# USBSerial.net
KiCad netlist of a schematic drawn in EAGLE
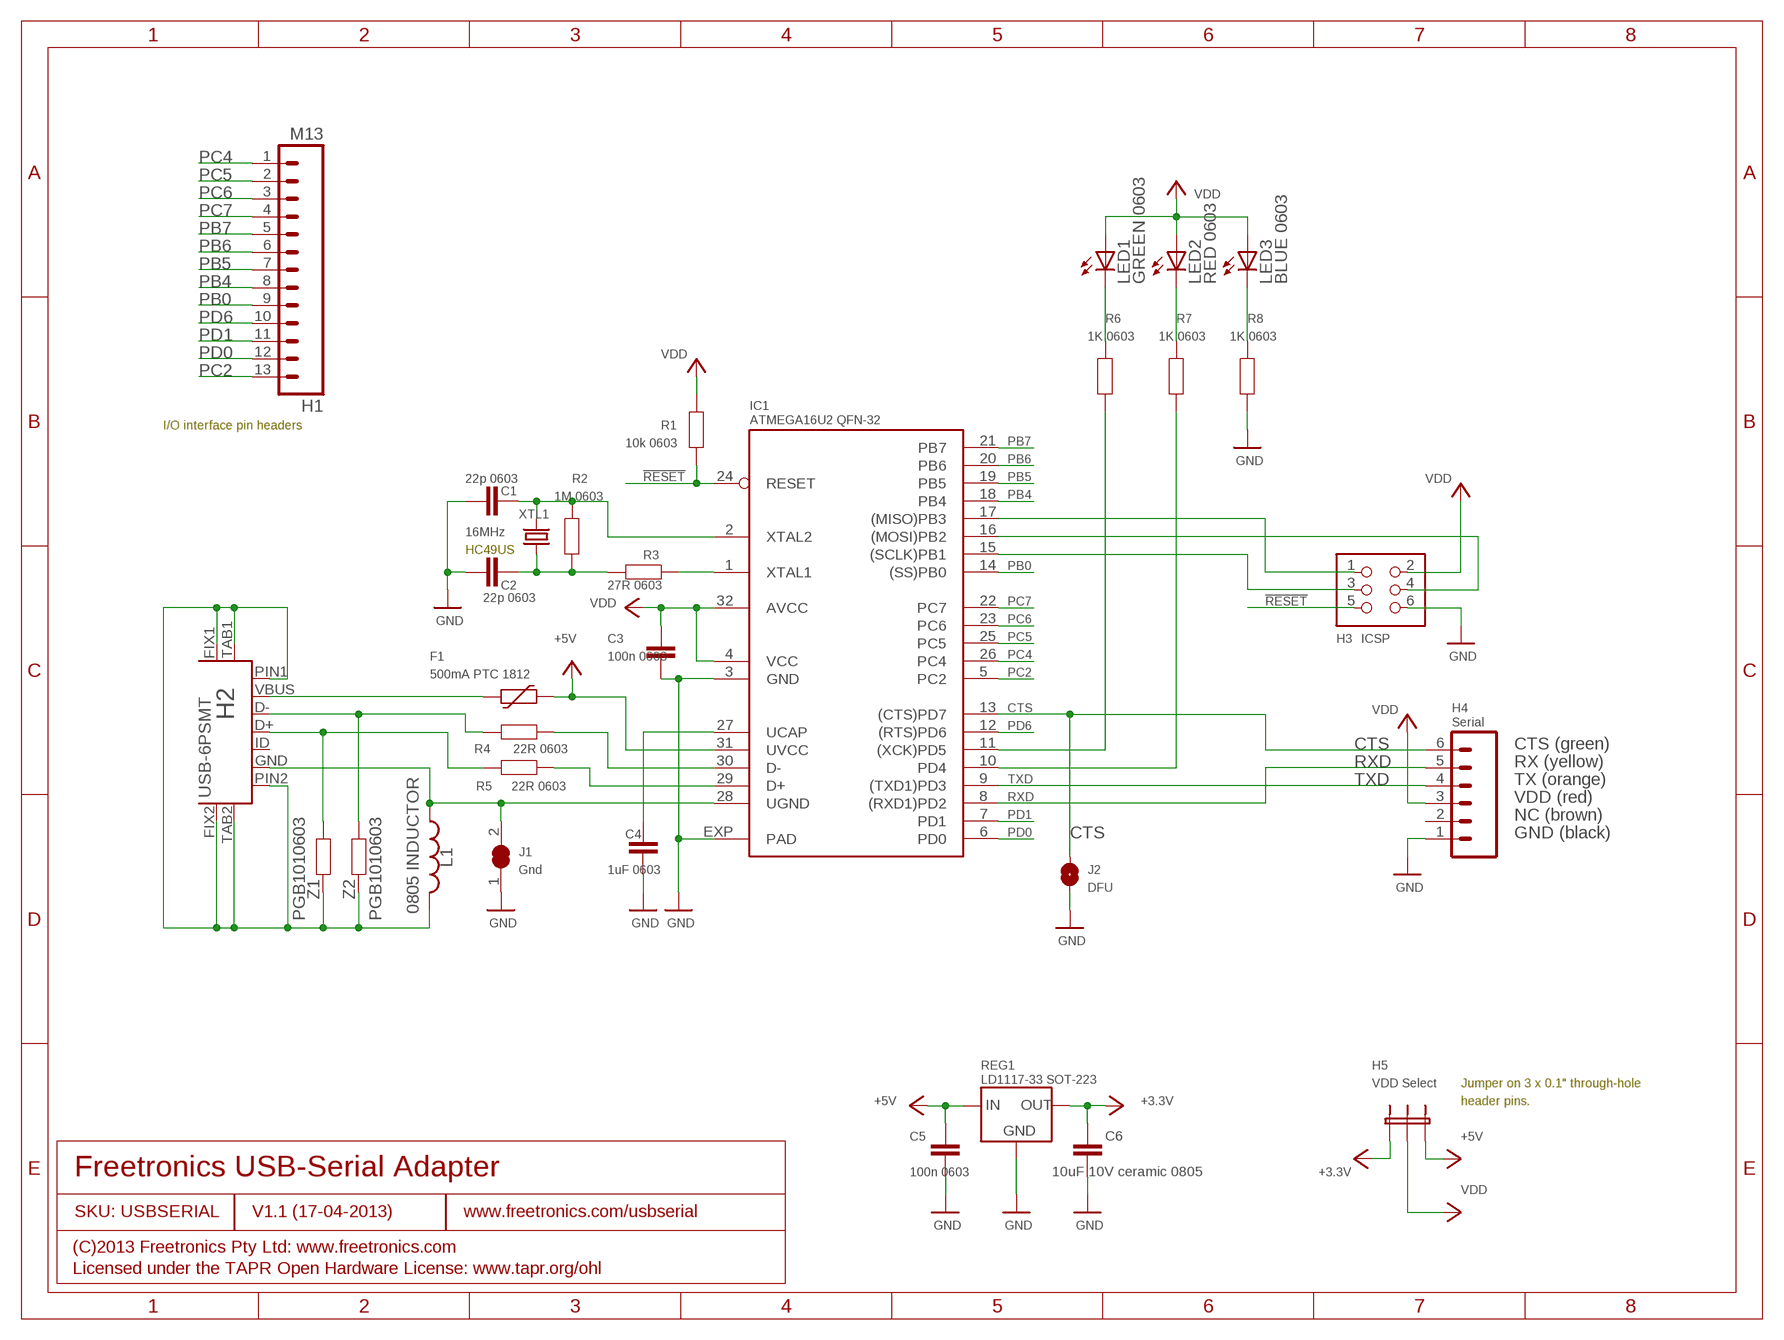
[diagram p0: schematic, sheet 1]

(export (version "E")
  (design (tool "Eeschema 10.0.6"))
  (components
    (comp (ref "C1")
      (value "22p 0603")
      (footprint "eagle-import:0603")
      (libsource (lib "eagle-import") (part "CAP0603"))
    )
    (comp (ref "C2")
      (value "22p 0603")
      (footprint "eagle-import:0603")
      (libsource (lib "eagle-import") (part "CAP0603"))
    )
    (comp (ref "C3")
      (value "100n 0603")
      (footprint "eagle-import:0603")
      (libsource (lib "eagle-import") (part "CAP0603"))
    )
    (comp (ref "C4")
      (value "1uF 0603")
      (footprint "eagle-import:0603")
      (libsource (lib "eagle-import") (part "CAP0603"))
    )
    (comp (ref "C5")
      (value "100n 0603")
      (footprint "eagle-import:0603")
      (libsource (lib "eagle-import") (part "CAP0603"))
    )
    (comp (ref "C6")
      (value "10uF 10V ceramic 0805")
      (footprint "eagle-import:C0805")
      (libsource (lib "eagle-import") (part "C-EUC0805"))
    )
    (comp (ref "F1")
      (value "500mA PTC 1812")
      (footprint "eagle-import:1812")
      (libsource (lib "eagle-import") (part "PTC"))
    )
    (comp (ref "H1")
      (value "M13")
      (footprint "eagle-import:1X13")
      (libsource (lib "eagle-import") (part "M13"))
    )
    (comp (ref "H2")
      (value "USB-6PSMT")
      (footprint "eagle-import:USB-MICROB-MB05PMXX")
      (libsource (lib "eagle-import") (part "USB-6PSMT"))
    )
    (comp (ref "H3")
      (value "ICSP")
      (footprint "eagle-import:HEADER_2X3")
      (libsource (lib "eagle-import") (part "HEADER_2X3"))
    )
    (comp (ref "H4")
      (value "Serial")
      (footprint "eagle-import:1X06")
      (libsource (lib "eagle-import") (part "M06SIP"))
    )
    (comp (ref "H5")
      (value "VDD Select")
      (footprint "eagle-import:JUMPER_SPDT")
      (libsource (lib "eagle-import") (part "JUMPER_SPDT"))
    )
    (comp (ref "IC1")
      (value "ATMEGA16U2 QFN-32")
      (footprint "eagle-import:ATMEL_QFN32")
      (libsource (lib "eagle-import") (part "ATMEL_ATMEGA8U2-MUQFN"))
    )
    (comp (ref "J1")
      (value "Gnd")
      (footprint "eagle-import:SJC")
      (libsource (lib "eagle-import") (part "SJCN"))
    )
    (comp (ref "J2") (value "DFU") (footprint "eagle-import:SJ") (libsource (lib "eagle-import") (part "SJ")))
    (comp (ref "L1")
      (value "0805 INDUCTOR")
      (footprint "eagle-import:0805-LARGE")
      (libsource (lib "eagle-import") (part "INDUCTOR0805-LARGE"))
    )
    (comp (ref "LED1")
      (value "GREEN 0603")
      (footprint "eagle-import:LED-0603")
      (libsource (lib "eagle-import") (part "LED0603"))
    )
    (comp (ref "LED2")
      (value "RED 0603")
      (footprint "eagle-import:LED-0603")
      (libsource (lib "eagle-import") (part "LED0603"))
    )
    (comp (ref "LED3")
      (value "BLUE 0603")
      (footprint "eagle-import:LED-0603")
      (libsource (lib "eagle-import") (part "LED0603"))
    )
    (comp (ref "R1")
      (value "10k 0603")
      (footprint "eagle-import:0603")
      (libsource (lib "eagle-import") (part "RESISTOR0603"))
    )
    (comp (ref "R2")
      (value "1M 0603")
      (footprint "eagle-import:0603")
      (libsource (lib "eagle-import") (part "RESISTOR0603"))
    )
    (comp (ref "R3")
      (value "27R 0603")
      (footprint "eagle-import:0603")
      (libsource (lib "eagle-import") (part "RESISTOR0603"))
    )
    (comp (ref "R4")
      (value "22R 0603")
      (footprint "eagle-import:0603")
      (libsource (lib "eagle-import") (part "RESISTOR0603"))
    )
    (comp (ref "R5")
      (value "22R 0603")
      (footprint "eagle-import:0603")
      (libsource (lib "eagle-import") (part "RESISTOR0603"))
    )
    (comp (ref "R6")
      (value "1K 0603")
      (footprint "eagle-import:0603")
      (libsource (lib "eagle-import") (part "RESISTOR0603"))
    )
    (comp (ref "R7")
      (value "1K 0603")
      (footprint "eagle-import:0603")
      (libsource (lib "eagle-import") (part "RESISTOR0603"))
    )
    (comp (ref "R8")
      (value "1K 0603")
      (footprint "eagle-import:0603")
      (libsource (lib "eagle-import") (part "RESISTOR0603"))
    )
    (comp (ref "REG1")
      (value "LD1117-33 SOT-223")
      (footprint "eagle-import:SOT-223")
      (libsource (lib "eagle-import") (part "LD1117-FIXED"))
    )
    (comp (ref "XTL1")
      (value "16MHz")
      (footprint "eagle-import:HC49US")
      (libsource (lib "eagle-import") (part "CRYSTALHC49US"))
    )
    (comp (ref "Z1")
      (value "PGB1010603")
      (footprint "eagle-import:0603")
      (libsource (lib "eagle-import") (part "RESISTOR0603"))
    )
    (comp (ref "Z2")
      (value "PGB1010603")
      (footprint "eagle-import:0603")
      (libsource (lib "eagle-import") (part "RESISTOR0603"))
    )
  )
  (nets
    (net (code "1") (name "+3.3V") (class "Default")
      (node (ref "C6") (pin "1") (pinfunction "1_1") (pintype "passive"))
      (node (ref "H5") (pin "1") (pinfunction "1_1") (pintype "passive"))
      (node (ref "REG1") (pin "2") (pinfunction "OUT_2") (pintype "power_in"))
      (node (ref "REG1") (pin "4") (pinfunction "OUT_4") (pintype "power_in"))
    )
    (net (code "2") (name "+5V") (class "Default")
      (node (ref "C5") (pin "1") (pinfunction "1_1") (pintype "passive"))
      (node (ref "F1") (pin "2") (pinfunction "P$2_2") (pintype "bidirectional"))
      (node (ref "H5") (pin "3") (pinfunction "3_3") (pintype "passive"))
      (node (ref "IC1") (pin "31") (pinfunction "UVCC_31") (pintype "power_in"))
      (node (ref "REG1") (pin "3") (pinfunction "IN_3") (pintype "input"))
    )
    (net (code "3") (name "/CTS") (class "Default")
      (node (ref "H4") (pin "6") (pinfunction "6_6") (pintype "passive"))
      (node (ref "IC1") (pin "13") (pinfunction "(CTS)PD7_13") (pintype "bidirectional"))
      (node (ref "J2") (pin "2") (pinfunction "2_2") (pintype "passive"))
    )
    (net (code "4") (name "/PB0") (class "Default")
      (node (ref "H1") (pin "9") (pinfunction "9_9") (pintype "passive"))
      (node (ref "IC1") (pin "14") (pinfunction "(SS)PB0_14") (pintype "bidirectional"))
    )
    (net (code "5") (name "/PB4") (class "Default")
      (node (ref "H1") (pin "8") (pinfunction "8_8") (pintype "passive"))
      (node (ref "IC1") (pin "18") (pinfunction "PB4_18") (pintype "bidirectional"))
    )
    (net (code "6") (name "/PB5") (class "Default")
      (node (ref "H1") (pin "7") (pinfunction "7_7") (pintype "passive"))
      (node (ref "IC1") (pin "19") (pinfunction "PB5_19") (pintype "bidirectional"))
    )
    (net (code "7") (name "/PB6") (class "Default")
      (node (ref "H1") (pin "6") (pinfunction "6_6") (pintype "passive"))
      (node (ref "IC1") (pin "20") (pinfunction "PB6_20") (pintype "bidirectional"))
    )
    (net (code "8") (name "/PB7") (class "Default")
      (node (ref "H1") (pin "5") (pinfunction "5_5") (pintype "passive"))
      (node (ref "IC1") (pin "21") (pinfunction "PB7_21") (pintype "bidirectional"))
    )
    (net (code "9") (name "/PC2") (class "Default")
      (node (ref "H1") (pin "13") (pinfunction "13_13") (pintype "passive"))
      (node (ref "IC1") (pin "5") (pinfunction "PC2_5") (pintype "bidirectional"))
    )
    (net (code "10") (name "/PC4") (class "Default")
      (node (ref "H1") (pin "1") (pinfunction "1_1") (pintype "passive"))
      (node (ref "IC1") (pin "26") (pinfunction "PC4_26") (pintype "bidirectional"))
    )
    (net (code "11") (name "/PC5") (class "Default")
      (node (ref "H1") (pin "2") (pinfunction "2_2") (pintype "passive"))
      (node (ref "IC1") (pin "25") (pinfunction "PC5_25") (pintype "bidirectional"))
    )
    (net (code "12") (name "/PC6") (class "Default")
      (node (ref "H1") (pin "3") (pinfunction "3_3") (pintype "passive"))
      (node (ref "IC1") (pin "23") (pinfunction "PC6_23") (pintype "bidirectional"))
    )
    (net (code "13") (name "/PC7") (class "Default")
      (node (ref "H1") (pin "4") (pinfunction "4_4") (pintype "passive"))
      (node (ref "IC1") (pin "22") (pinfunction "PC7_22") (pintype "bidirectional"))
    )
    (net (code "14") (name "/PD0") (class "Default")
      (node (ref "H1") (pin "12") (pinfunction "12_12") (pintype "passive"))
      (node (ref "IC1") (pin "6") (pinfunction "PD0_6") (pintype "bidirectional"))
    )
    (net (code "15") (name "/PD1") (class "Default")
      (node (ref "H1") (pin "11") (pinfunction "11_11") (pintype "passive"))
      (node (ref "IC1") (pin "7") (pinfunction "PD1_7") (pintype "bidirectional"))
    )
    (net (code "16") (name "/PD6") (class "Default")
      (node (ref "H1") (pin "10") (pinfunction "10_10") (pintype "passive"))
      (node (ref "IC1") (pin "12") (pinfunction "(RTS)PD6_12") (pintype "bidirectional"))
    )
    (net (code "17") (name "/RXD") (class "Default")
      (node (ref "H4") (pin "5") (pinfunction "5_5") (pintype "passive"))
      (node (ref "IC1") (pin "8") (pinfunction "(RXD1)PD2_8") (pintype "bidirectional"))
    )
    (net (code "18") (name "/TXD") (class "Default")
      (node (ref "H4") (pin "4") (pinfunction "4_4") (pintype "passive"))
      (node (ref "IC1") (pin "9") (pinfunction "(TXD1)PD3_9") (pintype "bidirectional"))
    )
    (net (code "19") (name "/~{RESET}") (class "Default")
      (node (ref "H3") (pin "5") (pinfunction "5_5") (pintype "passive"))
      (node (ref "IC1") (pin "24") (pinfunction "RESET_24") (pintype "input"))
      (node (ref "R1") (pin "1") (pinfunction "1_1") (pintype "passive"))
    )
    (net (code "20") (name "GND") (class "Default")
      (node (ref "C1") (pin "1") (pinfunction "1_1") (pintype "passive"))
      (node (ref "C2") (pin "1") (pinfunction "1_1") (pintype "passive"))
      (node (ref "C3") (pin "2") (pinfunction "2_2") (pintype "passive"))
      (node (ref "C4") (pin "2") (pinfunction "2_2") (pintype "passive"))
      (node (ref "C5") (pin "2") (pinfunction "2_2") (pintype "passive"))
      (node (ref "C6") (pin "2") (pinfunction "2_2") (pintype "passive"))
      (node (ref "H3") (pin "6") (pinfunction "6_6") (pintype "passive"))
      (node (ref "H4") (pin "1") (pinfunction "1_1") (pintype "passive"))
      (node (ref "IC1") (pin "3") (pinfunction "GND_3") (pintype "power_in"))
      (node (ref "IC1") (pin "EXP") (pinfunction "PAD_EXP") (pintype "power_in"))
      (node (ref "J1") (pin "1") (pinfunction "1_1") (pintype "passive"))
      (node (ref "J2") (pin "1") (pinfunction "1_1") (pintype "passive"))
      (node (ref "R8") (pin "1") (pinfunction "1_1") (pintype "passive"))
      (node (ref "REG1") (pin "1") (pinfunction "GND_1") (pintype "input"))
    )
    (net (code "21") (name "Net-(C2-Pad2)") (class "Default")
      (node (ref "C2") (pin "2") (pinfunction "2_2") (pintype "passive"))
      (node (ref "R2") (pin "1") (pinfunction "1_1") (pintype "passive"))
      (node (ref "R3") (pin "2") (pinfunction "2_2") (pintype "passive"))
      (node (ref "XTL1") (pin "1") (pinfunction "1_1") (pintype "passive"))
    )
    (net (code "22") (name "Net-(F1-P$1)") (class "Default")
      (node (ref "F1") (pin "1") (pinfunction "P$1_1") (pintype "bidirectional"))
      (node (ref "H2") (pin "VBUS") (pinfunction "VBUS_VBUS") (pintype "bidirectional"))
    )
    (net (code "23") (name "Net-(H2-PadD+)") (class "Default")
      (node (ref "H2") (pin "D+") (pinfunction "D+_D+") (pintype "bidirectional"))
      (node (ref "R5") (pin "2") (pinfunction "2_2") (pintype "passive"))
      (node (ref "Z1") (pin "1") (pinfunction "1_1") (pintype "passive"))
    )
    (net (code "24") (name "Net-(H2-PadD-)") (class "Default")
      (node (ref "H2") (pin "D-") (pinfunction "D-_D-") (pintype "bidirectional"))
      (node (ref "R4") (pin "2") (pinfunction "2_2") (pintype "passive"))
      (node (ref "Z2") (pin "1") (pinfunction "1_1") (pintype "passive"))
    )
    (net (code "25") (name "Net-(H2-PadFIX1)") (class "Default")
      (node (ref "H2") (pin "FIX1") (pinfunction "FIX1_FIX1") (pintype "bidirectional"))
      (node (ref "H2") (pin "FIX2") (pinfunction "FIX2_FIX2") (pintype "bidirectional"))
      (node (ref "H2") (pin "PIN1") (pinfunction "PIN1_PIN1") (pintype "bidirectional"))
      (node (ref "H2") (pin "PIN2") (pinfunction "PIN2_PIN2") (pintype "bidirectional"))
      (node (ref "H2") (pin "TAB1") (pinfunction "TAB1_TAB1") (pintype "bidirectional"))
      (node (ref "H2") (pin "TAB2") (pinfunction "TAB2_TAB2") (pintype "bidirectional"))
      (node (ref "L1") (pin "2") (pinfunction "2_2") (pintype "passive"))
      (node (ref "Z1") (pin "2") (pinfunction "2_2") (pintype "passive"))
      (node (ref "Z2") (pin "2") (pinfunction "2_2") (pintype "passive"))
    )
    (net (code "26") (name "Net-(IC1-(MISO)PB3)") (class "Default")
      (node (ref "H3") (pin "1") (pinfunction "1_1") (pintype "passive"))
      (node (ref "IC1") (pin "17") (pinfunction "(MISO)PB3_17") (pintype "bidirectional"))
    )
    (net (code "27") (name "Net-(IC1-(MOSI)PB2)") (class "Default")
      (node (ref "H3") (pin "4") (pinfunction "4_4") (pintype "passive"))
      (node (ref "IC1") (pin "16") (pinfunction "(MOSI)PB2_16") (pintype "bidirectional"))
    )
    (net (code "28") (name "Net-(IC1-(SCLK)PB1)") (class "Default")
      (node (ref "H3") (pin "3") (pinfunction "3_3") (pintype "passive"))
      (node (ref "IC1") (pin "15") (pinfunction "(SCLK)PB1_15") (pintype "bidirectional"))
    )
    (net (code "29") (name "Net-(IC1-(XCK)PD5)") (class "Default")
      (node (ref "IC1") (pin "11") (pinfunction "(XCK)PD5_11") (pintype "bidirectional"))
      (node (ref "R6") (pin "1") (pinfunction "1_1") (pintype "passive"))
    )
    (net (code "30") (name "Net-(IC1-D+)") (class "Default")
      (node (ref "IC1") (pin "29") (pinfunction "D+_29") (pintype "bidirectional"))
      (node (ref "R5") (pin "1") (pinfunction "1_1") (pintype "passive"))
    )
    (net (code "31") (name "Net-(IC1-D-)") (class "Default")
      (node (ref "IC1") (pin "30") (pinfunction "D-_30") (pintype "bidirectional"))
      (node (ref "R4") (pin "1") (pinfunction "1_1") (pintype "passive"))
    )
    (net (code "32") (name "Net-(IC1-PD4)") (class "Default")
      (node (ref "IC1") (pin "10") (pinfunction "PD4_10") (pintype "bidirectional"))
      (node (ref "R7") (pin "1") (pinfunction "1_1") (pintype "passive"))
    )
    (net (code "33") (name "Net-(IC1-UCAP)") (class "Default")
      (node (ref "C4") (pin "1") (pinfunction "1_1") (pintype "passive"))
      (node (ref "IC1") (pin "27") (pinfunction "UCAP_27") (pintype "passive"))
    )
    (net (code "34") (name "Net-(IC1-UGND)") (class "Default")
      (node (ref "H2") (pin "GND") (pinfunction "GND_GND") (pintype "bidirectional"))
      (node (ref "IC1") (pin "28") (pinfunction "UGND_28") (pintype "power_in"))
      (node (ref "J1") (pin "2") (pinfunction "2_2") (pintype "passive"))
      (node (ref "L1") (pin "1") (pinfunction "1_1") (pintype "passive"))
    )
    (net (code "35") (name "Net-(IC1-XTAL1)") (class "Default")
      (node (ref "IC1") (pin "1") (pinfunction "XTAL1_1") (pintype "bidirectional"))
      (node (ref "R3") (pin "1") (pinfunction "1_1") (pintype "passive"))
    )
    (net (code "36") (name "Net-(IC1-XTAL2)") (class "Default")
      (node (ref "C1") (pin "2") (pinfunction "2_2") (pintype "passive"))
      (node (ref "IC1") (pin "2") (pinfunction "XTAL2_2") (pintype "bidirectional"))
      (node (ref "R2") (pin "2") (pinfunction "2_2") (pintype "passive"))
      (node (ref "XTL1") (pin "2") (pinfunction "2_2") (pintype "passive"))
    )
    (net (code "37") (name "Net-(LED1-PadC)") (class "Default")
      (node (ref "LED1") (pin "C") (pinfunction "C_C") (pintype "passive"))
      (node (ref "R6") (pin "2") (pinfunction "2_2") (pintype "passive"))
    )
    (net (code "38") (name "Net-(LED2-PadC)") (class "Default")
      (node (ref "LED2") (pin "C") (pinfunction "C_C") (pintype "passive"))
      (node (ref "R7") (pin "2") (pinfunction "2_2") (pintype "passive"))
    )
    (net (code "39") (name "Net-(LED3-PadC)") (class "Default")
      (node (ref "LED3") (pin "C") (pinfunction "C_C") (pintype "passive"))
      (node (ref "R8") (pin "2") (pinfunction "2_2") (pintype "passive"))
    )
    (net (code "40") (name "VDD") (class "Default")
      (node (ref "C3") (pin "1") (pinfunction "1_1") (pintype "passive"))
      (node (ref "H3") (pin "2") (pinfunction "2_2") (pintype "passive"))
      (node (ref "H4") (pin "3") (pinfunction "3_3") (pintype "passive"))
      (node (ref "H5") (pin "2") (pinfunction "2_2") (pintype "passive"))
      (node (ref "IC1") (pin "32") (pinfunction "AVCC_32") (pintype "power_in"))
      (node (ref "IC1") (pin "4") (pinfunction "VCC_4") (pintype "power_in"))
      (node (ref "LED1") (pin "A") (pinfunction "A_A") (pintype "passive"))
      (node (ref "LED2") (pin "A") (pinfunction "A_A") (pintype "passive"))
      (node (ref "LED3") (pin "A") (pinfunction "A_A") (pintype "passive"))
      (node (ref "R1") (pin "2") (pinfunction "2_2") (pintype "passive"))
    )
    (net (code "41") (name "unconnected-(H2-PadID)") (class "Default")
      (node (ref "H2") (pin "ID") (pinfunction "ID_ID") (pintype "bidirectional"))
    )
    (net (code "42") (name "unconnected-(H4-Pad2)") (class "Default")
      (node (ref "H4") (pin "2") (pinfunction "2_2") (pintype "passive"))
    )
  )
)
